# maincont.net
KiCad netlist of a schematic drawn in Altium Designer
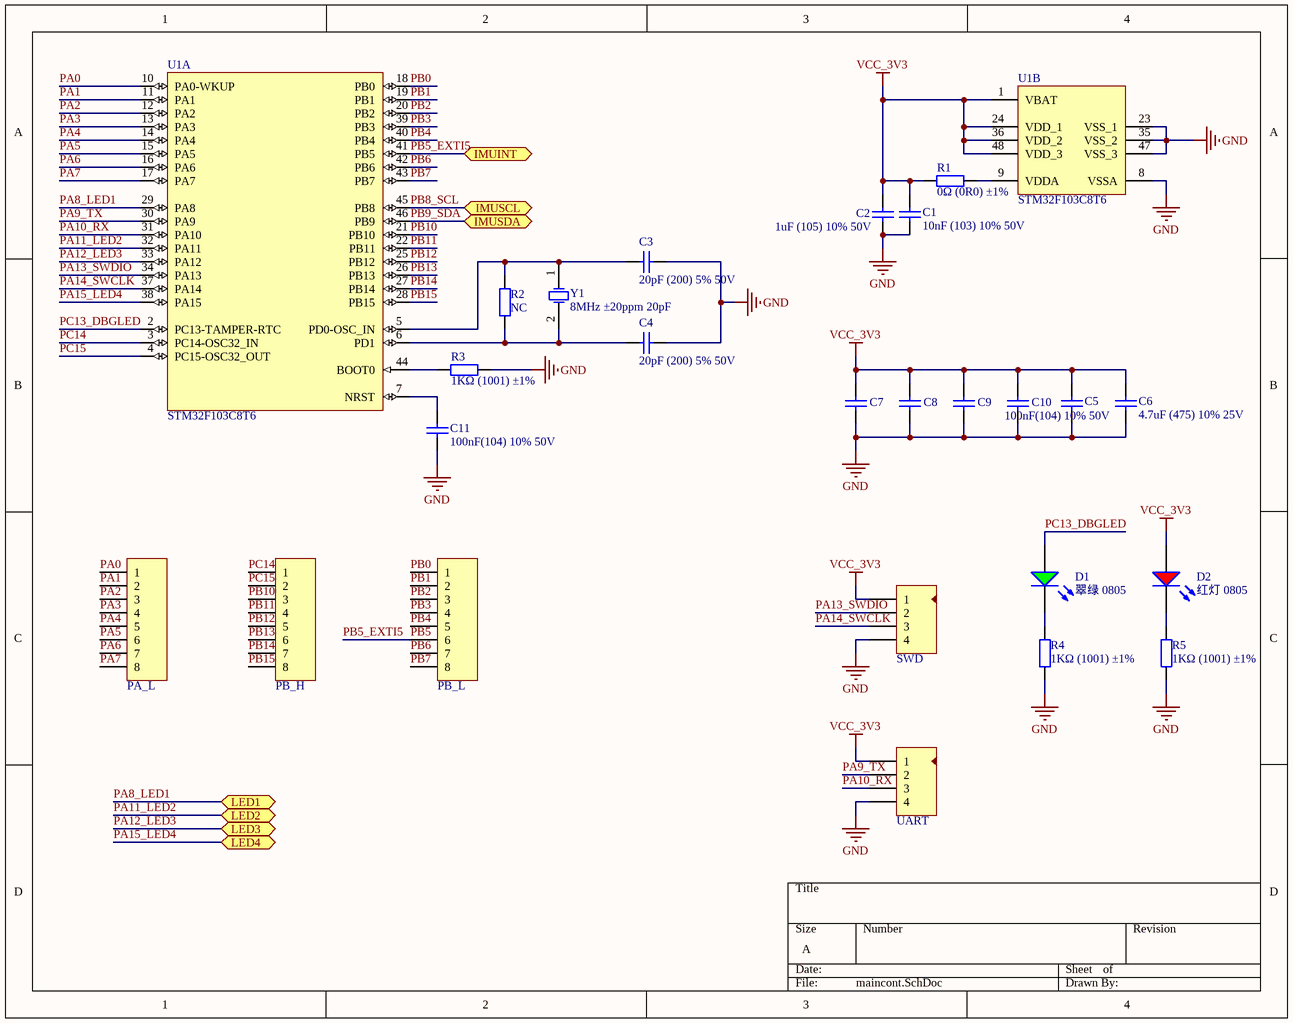
[diagram p0: maincont.SchDoc]

(export (version "E")
  (design (tool "Eeschema 10.0.6"))
  (components
    (comp (ref "C1")
      (value "10nF (103) 10% 50V")
      (footprint "LC-0805_C")
      (description "贴片电容")
      (libsource (lib "Miscellaneous Devices LC") (part "0805 10nF (103) 10% 50V"))
    )
    (comp (ref "C2")
      (value "1uF (105) 10% 50V")
      (footprint "LC-0805_C")
      (description "贴片电容")
      (libsource (lib "Miscellaneous Devices LC") (part "0805 1uF (105) 10% 50V"))
    )
    (comp (ref "C3")
      (value "20pF (200) 5% 50V")
      (footprint "LC-0805_C")
      (description "贴片电容")
      (libsource (lib "Miscellaneous Devices LC") (part "0805 20pF (200) 5% 50V"))
    )
    (comp (ref "C4")
      (value "20pF (200) 5% 50V")
      (footprint "LC-0805_C")
      (description "贴片电容")
      (libsource (lib "Miscellaneous Devices LC") (part "0805 20pF (200) 5% 50V"))
    )
    (comp (ref "C5")
      (value "100nF(104) 10% 50V")
      (footprint "LC-0805_C")
      (description "贴片电容")
      (libsource (lib "Miscellaneous Devices LC") (part "0805 100nF(104) 10% 50V"))
    )
    (comp (ref "C6")
      (value "4.7uF (475) 10% 25V")
      (footprint "LC-0805_C")
      (description "贴片电容")
      (libsource (lib "Miscellaneous Devices LC") (part "0805 4.7uF (475) 10% 25V"))
    )
    (comp (ref "C7")
      (value "100nF(104) 10% 50V")
      (footprint "LC-0805_C")
      (description "贴片电容")
      (libsource (lib "Miscellaneous Devices LC") (part "0805 100nF(104) 10% 50V"))
    )
    (comp (ref "C8")
      (value "100nF(104) 10% 50V")
      (footprint "LC-0805_C")
      (description "贴片电容")
      (libsource (lib "Miscellaneous Devices LC") (part "0805 100nF(104) 10% 50V"))
    )
    (comp (ref "C9")
      (value "100nF(104) 10% 50V")
      (footprint "LC-0805_C")
      (description "贴片电容")
      (libsource (lib "Miscellaneous Devices LC") (part "0805 100nF(104) 10% 50V"))
    )
    (comp (ref "C10")
      (value "100nF(104) 10% 50V")
      (footprint "LC-0805_C")
      (description "贴片电容")
      (libsource (lib "Miscellaneous Devices LC") (part "0805 100nF(104) 10% 50V"))
    )
    (comp (ref "C11")
      (value "100nF(104) 10% 50V")
      (footprint "LC-0805_C")
      (description "贴片电容")
      (libsource (lib "Miscellaneous Devices LC") (part "0805 100nF(104) 10% 50V"))
    )
    (comp (ref "D1")
      (value "翠绿 0805")
      (footprint "LC-0805_LED_S1")
      (description "发光二极管")
      (libsource (lib "Miscellaneous Devices LC") (part "0805 翠绿"))
    )
    (comp (ref "D2")
      (value "红灯 0805")
      (footprint "LC-0805_LED_S1")
      (description "发光二极管")
      (libsource (lib "Miscellaneous Devices LC") (part "0805 红灯"))
    )
    (comp (ref "P1")
      (value "PA_L")
      (footprint "HDR1X8")
      (description "Header, 8-Pin")
      (fields (field (name "PUBLISHER") "Altium Limited"))
      (libsource (lib "Miscellaneous Connectors") (part "Header 8"))
    )
    (comp (ref "P2")
      (value "PB_H")
      (footprint "HDR1X8")
      (description "Header, 8-Pin")
      (fields (field (name "PUBLISHER") "Altium Limited"))
      (libsource (lib "Miscellaneous Connectors") (part "Header 8"))
    )
    (comp (ref "P3")
      (value "PB_L")
      (footprint "HDR1X8")
      (description "Header, 8-Pin")
      (fields (field (name "PUBLISHER") "Altium Limited"))
      (libsource (lib "Miscellaneous Connectors") (part "Header 8"))
    )
    (comp (ref "P4")
      (value "SWD")
      (footprint "HDR4X1-2.54")
      (description "接插件")
      (fields (field (name "PUBLISHER") "Altium Limited"))
      (libsource (lib "HDR_Fszhang") (part "Header 4"))
    )
    (comp (ref "P5")
      (value "UART")
      (footprint "HDR4X1-2.54")
      (description "接插件")
      (fields (field (name "PUBLISHER") "Altium Limited"))
      (libsource (lib "HDR_Fszhang") (part "Header 4"))
    )
    (comp (ref "R1")
      (value "0Ω (0R0) ±1%")
      (footprint "LC-0805_R")
      (description "贴片电阻")
      (libsource (lib "Miscellaneous Devices LC") (part "0805 0Ω (0R0) 1%"))
    )
    (comp (ref "R2")
      (value "NC")
      (footprint "LC-0805_R")
      (description "贴片电阻")
      (libsource (lib "Miscellaneous Devices LC") (part "0805 1MΩ (1004) 1%"))
    )
    (comp (ref "R3")
      (value "1KΩ (1001) ±1%")
      (footprint "LC-0805_R")
      (description "贴片电阻")
      (libsource (lib "Miscellaneous Devices LC") (part "0805 1KΩ (1001) 1%"))
    )
    (comp (ref "R4")
      (value "1KΩ (1001) ±1%")
      (footprint "LC-0805_R")
      (description "贴片电阻")
      (libsource (lib "") (part "0805 1KΩ (1001) 1%_1"))
    )
    (comp (ref "R5")
      (value "1KΩ (1001) ±1%")
      (footprint "LC-0805_R")
      (description "贴片电阻")
      (libsource (lib "") (part "0805 1KΩ (1001) 1%_1"))
    )
    (comp (ref "U1")
      (value "STM32F103C8T6")
      (footprint "LC-LQFP-48_7x7x05P")
      (description "ARM")
      (libsource (lib "Miscellaneous Devices LC") (part "STM32F103C8T6"))
    )
    (comp (ref "Y1")
      (value "8MHz ±20ppm 20pF")
      (footprint "LC-SMD-5032_2P")
      (description "贴片晶振")
      (libsource (lib "Miscellaneous Devices LC") (part "SMD-5032_2P 8MHz 20ppm 20pF"))
    )
  )
  (nets
    (net (code "1") (name "/PA0") (class "Default")
      (node (ref "P1") (pin "1") (pinfunction "1_1") (pintype "passive"))
      (node (ref "U1") (pin "10") (pinfunction "PA0-WKUP_10") (pintype "bidirectional"))
    )
    (net (code "2") (name "/PA1") (class "Default")
      (node (ref "P1") (pin "2") (pinfunction "2_2") (pintype "passive"))
      (node (ref "U1") (pin "11") (pinfunction "PA1_11") (pintype "bidirectional"))
    )
    (net (code "3") (name "/PA2") (class "Default")
      (node (ref "P1") (pin "3") (pinfunction "3_3") (pintype "passive"))
      (node (ref "U1") (pin "12") (pinfunction "PA2_12") (pintype "bidirectional"))
    )
    (net (code "4") (name "/PA3") (class "Default")
      (node (ref "P1") (pin "4") (pinfunction "4_4") (pintype "passive"))
      (node (ref "U1") (pin "13") (pinfunction "PA3_13") (pintype "bidirectional"))
    )
    (net (code "5") (name "/PA4") (class "Default")
      (node (ref "P1") (pin "5") (pinfunction "5_5") (pintype "passive"))
      (node (ref "U1") (pin "14") (pinfunction "PA4_14") (pintype "bidirectional"))
    )
    (net (code "6") (name "/PA5") (class "Default")
      (node (ref "P1") (pin "6") (pinfunction "6_6") (pintype "passive"))
      (node (ref "U1") (pin "15") (pinfunction "PA5_15") (pintype "bidirectional"))
    )
    (net (code "7") (name "/PA6") (class "Default")
      (node (ref "P1") (pin "7") (pinfunction "7_7") (pintype "passive"))
      (node (ref "U1") (pin "16") (pinfunction "PA6_16") (pintype "bidirectional"))
    )
    (net (code "8") (name "/PA7") (class "Default")
      (node (ref "P1") (pin "8") (pinfunction "8_8") (pintype "passive"))
      (node (ref "U1") (pin "17") (pinfunction "PA7_17") (pintype "bidirectional"))
    )
    (net (code "9") (name "/PA8_LED1") (class "Default")
      (node (ref "U1") (pin "29") (pinfunction "PA8_29") (pintype "bidirectional"))
    )
    (net (code "10") (name "/PA9_TX") (class "Default")
      (node (ref "P5") (pin "2") (pinfunction "2_2") (pintype "passive"))
      (node (ref "U1") (pin "30") (pinfunction "PA9_30") (pintype "bidirectional"))
    )
    (net (code "11") (name "/PA10_RX") (class "Default")
      (node (ref "P5") (pin "3") (pinfunction "3_3") (pintype "passive"))
      (node (ref "U1") (pin "31") (pinfunction "PA10_31") (pintype "bidirectional"))
    )
    (net (code "12") (name "/PA11_LED2") (class "Default")
      (node (ref "U1") (pin "32") (pinfunction "PA11_32") (pintype "bidirectional"))
    )
    (net (code "13") (name "/PA12_LED3") (class "Default")
      (node (ref "U1") (pin "33") (pinfunction "PA12_33") (pintype "bidirectional"))
    )
    (net (code "14") (name "/PA13_SWDIO") (class "Default")
      (node (ref "P4") (pin "2") (pinfunction "2_2") (pintype "passive"))
      (node (ref "U1") (pin "34") (pinfunction "PA13_34") (pintype "bidirectional"))
    )
    (net (code "15") (name "/PA14_SWCLK") (class "Default")
      (node (ref "P4") (pin "3") (pinfunction "3_3") (pintype "passive"))
      (node (ref "U1") (pin "37") (pinfunction "PA14_37") (pintype "bidirectional"))
    )
    (net (code "16") (name "/PA15_LED4") (class "Default")
      (node (ref "U1") (pin "38") (pinfunction "PA15_38") (pintype "bidirectional"))
    )
    (net (code "17") (name "/PB0") (class "Default")
      (node (ref "P3") (pin "1") (pinfunction "1_1") (pintype "passive"))
      (node (ref "U1") (pin "18") (pinfunction "PB0_18") (pintype "bidirectional"))
    )
    (net (code "18") (name "/PB1") (class "Default")
      (node (ref "P3") (pin "2") (pinfunction "2_2") (pintype "passive"))
      (node (ref "U1") (pin "19") (pinfunction "PB1_19") (pintype "bidirectional"))
    )
    (net (code "19") (name "/PB2") (class "Default")
      (node (ref "P3") (pin "3") (pinfunction "3_3") (pintype "passive"))
      (node (ref "U1") (pin "20") (pinfunction "PB2_20") (pintype "bidirectional"))
    )
    (net (code "20") (name "/PB3") (class "Default")
      (node (ref "P3") (pin "4") (pinfunction "4_4") (pintype "passive"))
      (node (ref "U1") (pin "39") (pinfunction "PB3_39") (pintype "bidirectional"))
    )
    (net (code "21") (name "/PB4") (class "Default")
      (node (ref "P3") (pin "5") (pinfunction "5_5") (pintype "passive"))
      (node (ref "U1") (pin "40") (pinfunction "PB4_40") (pintype "bidirectional"))
    )
    (net (code "22") (name "/PB5") (class "Default")
      (node (ref "P3") (pin "6") (pinfunction "6_6") (pintype "passive"))
      (node (ref "U1") (pin "41") (pinfunction "PB5_41") (pintype "bidirectional"))
    )
    (net (code "23") (name "/PB6") (class "Default")
      (node (ref "P3") (pin "7") (pinfunction "7_7") (pintype "passive"))
      (node (ref "U1") (pin "42") (pinfunction "PB6_42") (pintype "bidirectional"))
    )
    (net (code "24") (name "/PB7") (class "Default")
      (node (ref "P3") (pin "8") (pinfunction "8_8") (pintype "passive"))
      (node (ref "U1") (pin "43") (pinfunction "PB7_43") (pintype "bidirectional"))
    )
    (net (code "25") (name "/PB8_SCL") (class "Default")
      (node (ref "U1") (pin "45") (pinfunction "PB8_45") (pintype "bidirectional"))
    )
    (net (code "26") (name "/PB9_SDA") (class "Default")
      (node (ref "U1") (pin "46") (pinfunction "PB9_46") (pintype "bidirectional"))
    )
    (net (code "27") (name "/PB10") (class "Default")
      (node (ref "P2") (pin "3") (pinfunction "3_3") (pintype "passive"))
      (node (ref "U1") (pin "21") (pinfunction "PB10_21") (pintype "bidirectional"))
    )
    (net (code "28") (name "/PB11") (class "Default")
      (node (ref "P2") (pin "4") (pinfunction "4_4") (pintype "passive"))
      (node (ref "U1") (pin "22") (pinfunction "PB11_22") (pintype "bidirectional"))
    )
    (net (code "29") (name "/PB12") (class "Default")
      (node (ref "P2") (pin "5") (pinfunction "5_5") (pintype "passive"))
      (node (ref "U1") (pin "25") (pinfunction "PB12_25") (pintype "bidirectional"))
    )
    (net (code "30") (name "/PB13") (class "Default")
      (node (ref "P2") (pin "6") (pinfunction "6_6") (pintype "passive"))
      (node (ref "U1") (pin "26") (pinfunction "PB13_26") (pintype "bidirectional"))
    )
    (net (code "31") (name "/PB14") (class "Default")
      (node (ref "P2") (pin "7") (pinfunction "7_7") (pintype "passive"))
      (node (ref "U1") (pin "27") (pinfunction "PB14_27") (pintype "bidirectional"))
    )
    (net (code "32") (name "/PB15") (class "Default")
      (node (ref "P2") (pin "8") (pinfunction "8_8") (pintype "passive"))
      (node (ref "U1") (pin "28") (pinfunction "PB15_28") (pintype "bidirectional"))
    )
    (net (code "33") (name "/PC13_DBGLED") (class "Default")
      (node (ref "D1") (pin "A") (pinfunction "A_A") (pintype "passive"))
      (node (ref "U1") (pin "2") (pinfunction "PC13-TAMPER-RTC_2") (pintype "bidirectional"))
    )
    (net (code "34") (name "/PC14") (class "Default")
      (node (ref "P2") (pin "1") (pinfunction "1_1") (pintype "passive"))
      (node (ref "U1") (pin "3") (pinfunction "PC14-OSC32_IN_3") (pintype "bidirectional"))
    )
    (net (code "35") (name "/PC15") (class "Default")
      (node (ref "P2") (pin "2") (pinfunction "2_2") (pintype "passive"))
      (node (ref "U1") (pin "4") (pinfunction "PC15-OSC32_OUT_4") (pintype "bidirectional"))
    )
    (net (code "36") (name "GND") (class "Default")
      (node (ref "C1") (pin "1") (pinfunction "1_1") (pintype "passive"))
      (node (ref "C10") (pin "2") (pinfunction "2_2") (pintype "passive"))
      (node (ref "C11") (pin "1") (pinfunction "1_1") (pintype "passive"))
      (node (ref "C2") (pin "1") (pinfunction "1_1") (pintype "passive"))
      (node (ref "C3") (pin "2") (pinfunction "2_2") (pintype "passive"))
      (node (ref "C4") (pin "2") (pinfunction "2_2") (pintype "passive"))
      (node (ref "C5") (pin "2") (pinfunction "2_2") (pintype "passive"))
      (node (ref "C6") (pin "1") (pinfunction "1_1") (pintype "passive"))
      (node (ref "C7") (pin "2") (pinfunction "2_2") (pintype "passive"))
      (node (ref "C8") (pin "2") (pinfunction "2_2") (pintype "passive"))
      (node (ref "C9") (pin "2") (pinfunction "2_2") (pintype "passive"))
      (node (ref "P4") (pin "4") (pinfunction "4_4") (pintype "passive"))
      (node (ref "P5") (pin "4") (pinfunction "4_4") (pintype "passive"))
      (node (ref "R3") (pin "2") (pinfunction "2_2") (pintype "passive"))
      (node (ref "R4") (pin "1") (pinfunction "1_1") (pintype "passive"))
      (node (ref "R5") (pin "1") (pinfunction "1_1") (pintype "passive"))
      (node (ref "U1") (pin "23") (pinfunction "VSS_1_23") (pintype "power_in"))
      (node (ref "U1") (pin "35") (pinfunction "VSS_2_35") (pintype "power_in"))
      (node (ref "U1") (pin "47") (pinfunction "VSS_3_47") (pintype "power_in"))
      (node (ref "U1") (pin "8") (pinfunction "VSSA_8") (pintype "power_in"))
    )
    (net (code "37") (name "Net-(D1-PadK)") (class "Default")
      (node (ref "D1") (pin "K") (pinfunction "K_K") (pintype "passive"))
      (node (ref "R4") (pin "2") (pinfunction "2_2") (pintype "passive"))
    )
    (net (code "38") (name "Net-(D2-PadK)") (class "Default")
      (node (ref "D2") (pin "K") (pinfunction "K_K") (pintype "passive"))
      (node (ref "R5") (pin "2") (pinfunction "2_2") (pintype "passive"))
    )
    (net (code "39") (name "Net-(U1A-BOOT0)") (class "Default")
      (node (ref "R3") (pin "1") (pinfunction "1_1") (pintype "passive"))
      (node (ref "U1") (pin "44") (pinfunction "BOOT0_44") (pintype "input"))
    )
    (net (code "40") (name "Net-(U1A-NRST)") (class "Default")
      (node (ref "C11") (pin "2") (pinfunction "2_2") (pintype "passive"))
      (node (ref "U1") (pin "7") (pinfunction "NRST_7") (pintype "bidirectional"))
    )
    (net (code "41") (name "Net-(U1A-PD0-OSC_IN)") (class "Default")
      (node (ref "C3") (pin "1") (pinfunction "1_1") (pintype "passive"))
      (node (ref "R2") (pin "1") (pinfunction "1_1") (pintype "passive"))
      (node (ref "U1") (pin "5") (pinfunction "PD0-OSC_IN_5") (pintype "bidirectional"))
      (node (ref "Y1") (pin "1") (pinfunction "OSC1_1") (pintype "passive"))
    )
    (net (code "42") (name "Net-(U1A-PD1)") (class "Default")
      (node (ref "C4") (pin "1") (pinfunction "1_1") (pintype "passive"))
      (node (ref "R2") (pin "2") (pinfunction "2_2") (pintype "passive"))
      (node (ref "U1") (pin "6") (pinfunction "PD1_6") (pintype "bidirectional"))
      (node (ref "Y1") (pin "2") (pinfunction "OSC2_2") (pintype "passive"))
    )
    (net (code "43") (name "Net-(U1B-VDDA)") (class "Default")
      (node (ref "R1") (pin "1") (pinfunction "1_1") (pintype "passive"))
      (node (ref "U1") (pin "9") (pinfunction "VDDA_9") (pintype "power_in"))
    )
    (net (code "44") (name "VCC_3V3") (class "Default")
      (node (ref "C1") (pin "2") (pinfunction "2_2") (pintype "passive"))
      (node (ref "C10") (pin "1") (pinfunction "1_1") (pintype "passive"))
      (node (ref "C2") (pin "2") (pinfunction "2_2") (pintype "passive"))
      (node (ref "C5") (pin "1") (pinfunction "1_1") (pintype "passive"))
      (node (ref "C6") (pin "2") (pinfunction "2_2") (pintype "passive"))
      (node (ref "C7") (pin "1") (pinfunction "1_1") (pintype "passive"))
      (node (ref "C8") (pin "1") (pinfunction "1_1") (pintype "passive"))
      (node (ref "C9") (pin "1") (pinfunction "1_1") (pintype "passive"))
      (node (ref "D2") (pin "A") (pinfunction "A_A") (pintype "passive"))
      (node (ref "P4") (pin "1") (pinfunction "1_1") (pintype "passive"))
      (node (ref "P5") (pin "1") (pinfunction "1_1") (pintype "passive"))
      (node (ref "R1") (pin "2") (pinfunction "2_2") (pintype "passive"))
      (node (ref "U1") (pin "1") (pinfunction "VBAT_1") (pintype "power_in"))
      (node (ref "U1") (pin "24") (pinfunction "VDD_1_24") (pintype "power_in"))
      (node (ref "U1") (pin "36") (pinfunction "VDD_2_36") (pintype "power_in"))
      (node (ref "U1") (pin "48") (pinfunction "VDD_3_48") (pintype "power_in"))
    )
  )
)
